# DigitalSignal.net
KiCad netlist of a schematic drawn in Altium Designer
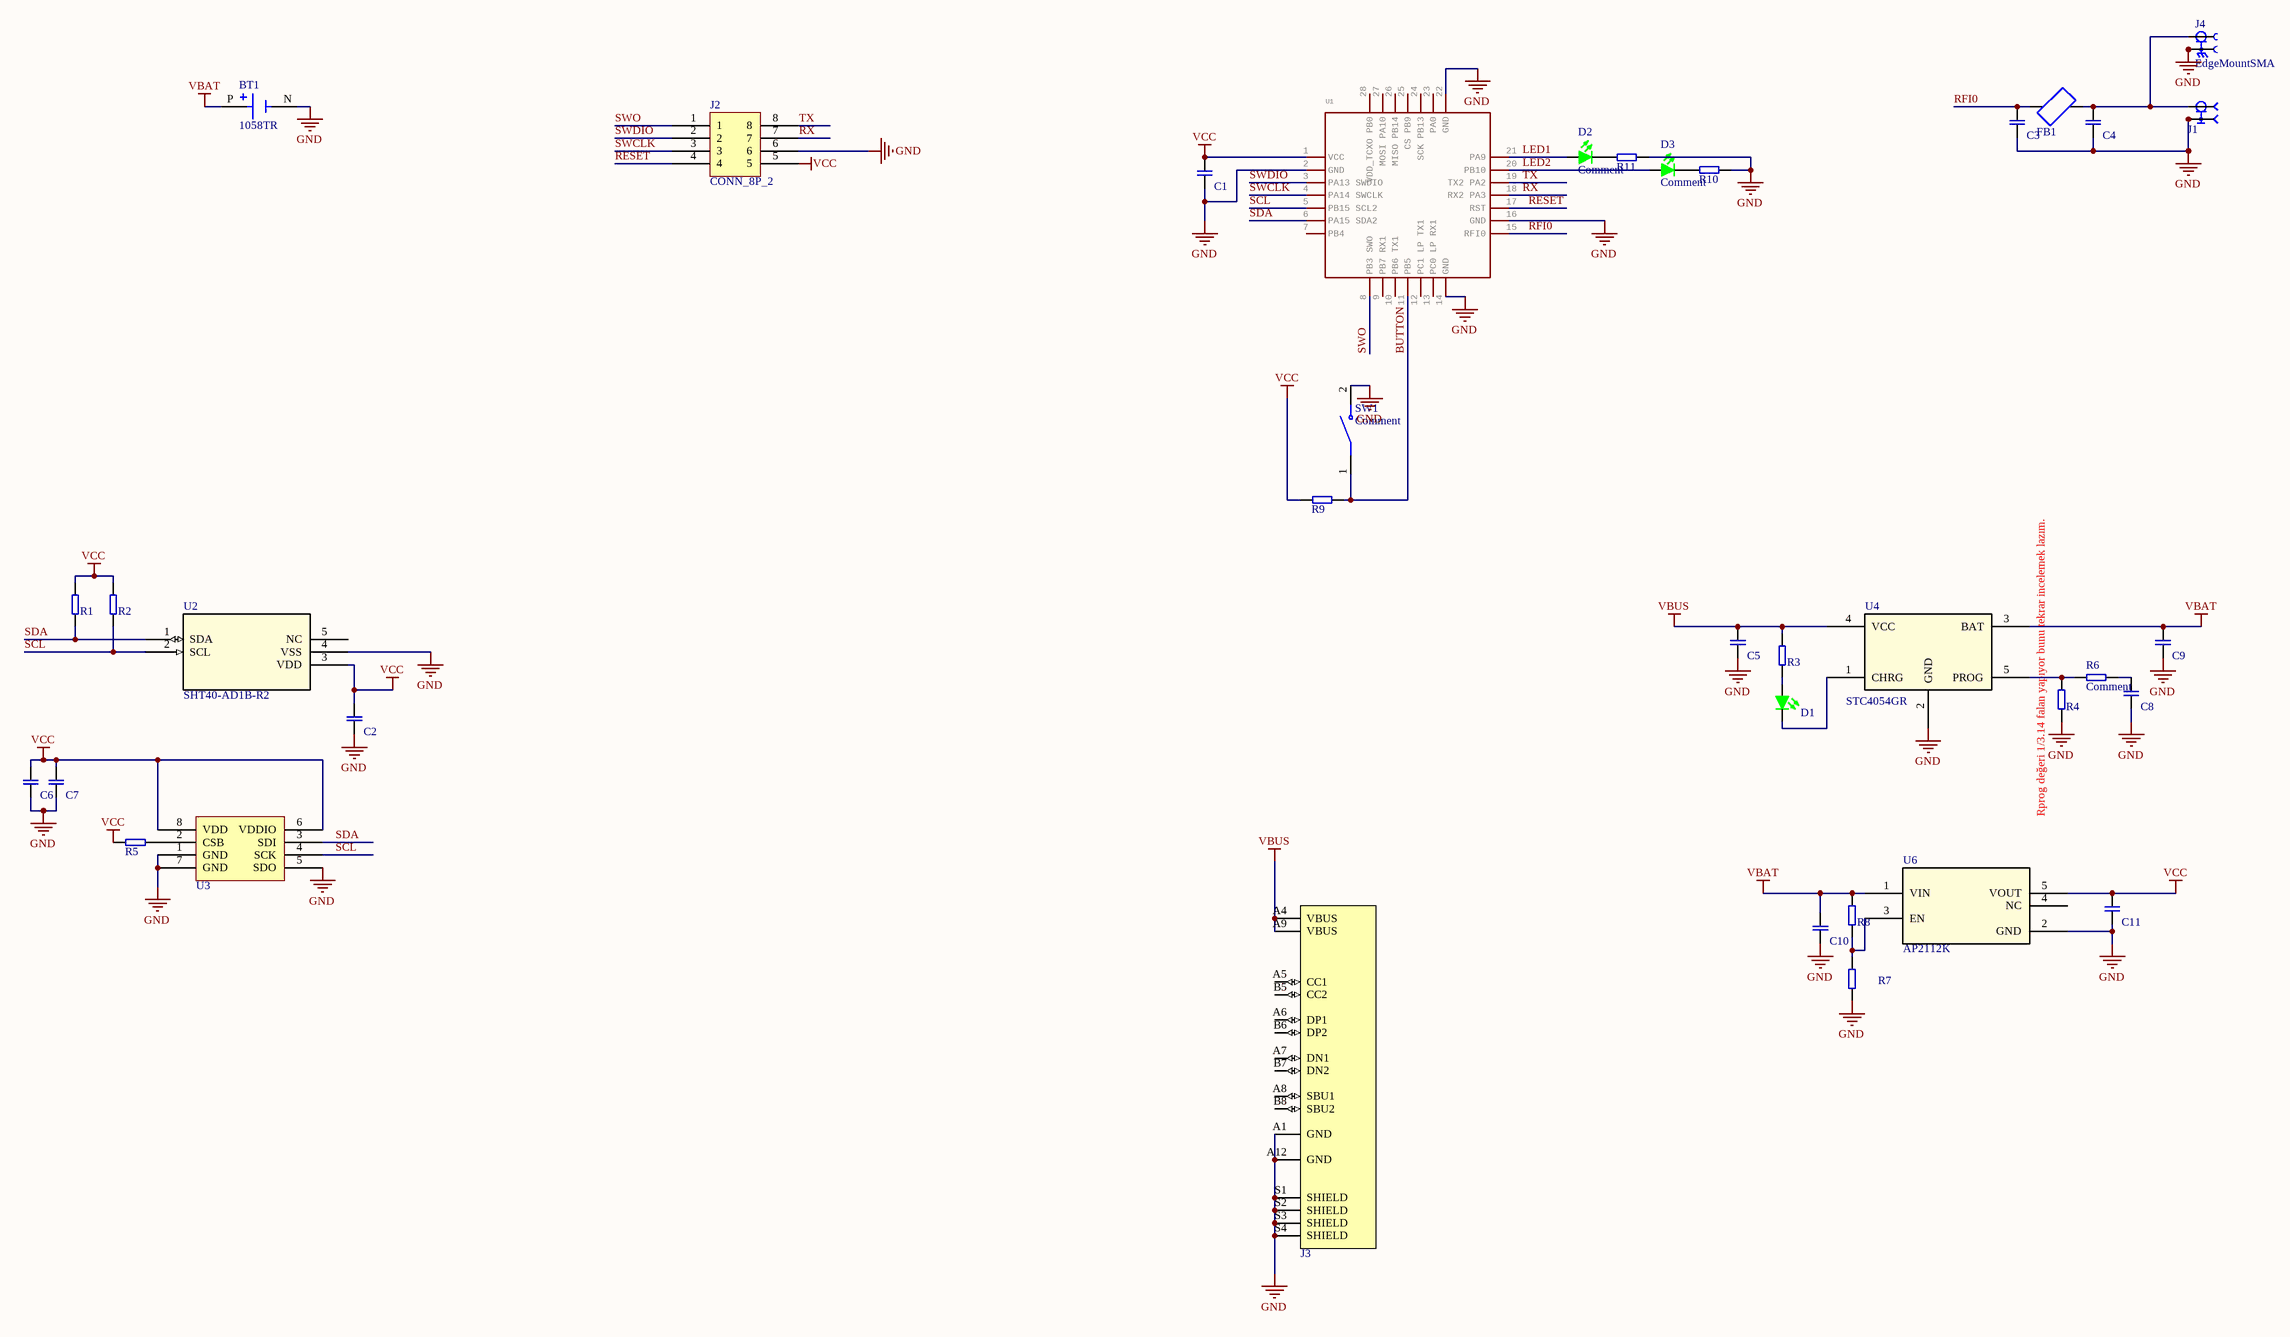
[diagram p0: DigitalSignal.SchDoc]

(export (version "E")
  (design (tool "Eeschema 10.0.6"))
  (components
    (comp (ref "BT1")
      (value "1058TR")
      (footprint "BAT_1058TR")
      (fields (field (name "PART NUMBER") "20mm_BatteryHolder"))
      (libsource (lib "anayurt") (part "1058TR"))
    )
    (comp (ref "C1")
      (value "4.7nF")
      (footprint "C0402")
      (description "CAP CER 4700PF 16V X7R 0402")
      (fields (field (name "PART NUMBER") "0402YC472KAT2A") (field (name "VOLTAGE") "16V"))
      (libsource (lib "anayurt") (part "CAP"))
    )
    (comp (ref "C2")
      (value "100nF")
      (footprint "C0402")
      (description "402")
      (fields (field (name "PART NUMBER") "CL05B104KB5NNNC"))
      (libsource (lib "anayurt") (part "CAP"))
    )
    (comp (ref "C3")
      (value "0.1uF")
      (footprint "C0402")
      (description "CAP CER 0.1UF 25V X7R 0402")
      (fields (field (name "PART NUMBER") "04023C104KAT2A") (field (name "VOLTAGE") "25V"))
      (libsource (lib "anayurt") (part "CAP"))
    )
    (comp (ref "C4")
      (value "0.1uF")
      (footprint "C0402")
      (description "CAP CER 0.1UF 25V X7R 0402")
      (fields (field (name "PART NUMBER") "04023C104KAT2A") (field (name "VOLTAGE") "25V"))
      (libsource (lib "anayurt") (part "CAP"))
    )
    (comp (ref "C5")
      (value "1uF")
      (footprint "C0603")
      (description "CAP CER 1UF 25V X7R 0603")
      (fields (field (name "PART NUMBER") "CGA3E1X7R1E105M080AC") (field (name "VOLTAGE") "25V"))
      (libsource (lib "anayurt") (part "CAP"))
    )
    (comp (ref "C6")
      (value "1uF")
      (footprint "C0402")
      (description "CAP CER 1UF 16V X5R 0402")
      (fields (field (name "PART NUMBER") "CL05A105KO5NNNC") (field (name "VOLTAGE") "16V"))
      (libsource (lib "anayurt") (part "CAP"))
    )
    (comp (ref "C7")
      (value "0.1uF")
      (footprint "C0402")
      (description "CAP CER 0.1UF 25V X7R 0402")
      (fields (field (name "PART NUMBER") "04023C104KAT2A") (field (name "VOLTAGE") "25V"))
      (libsource (lib "anayurt") (part "CAP"))
    )
    (comp (ref "C8")
      (value "100nF")
      (footprint "C0402")
      (description "402")
      (fields (field (name "PART NUMBER") "CL05B104KB5NNNC"))
      (libsource (lib "anayurt") (part "CAP"))
    )
    (comp (ref "C9")
      (value "4.7uF")
      (footprint "C0603")
      (description "CAP CER 4.7UF 25V X5R 0603")
      (fields (field (name "PART NUMBER") "C1608X5R1E475K080AC") (field (name "VOLTAGE") "25V"))
      (libsource (lib "anayurt") (part "CAP"))
    )
    (comp (ref "C10")
      (value "1uF")
      (footprint "C0402")
      (description "CAP CER 1UF 16V X5R 0402")
      (fields (field (name "PART NUMBER") "CL05A105KO5NNNC") (field (name "VOLTAGE") "16V"))
      (libsource (lib "anayurt") (part "CAP"))
    )
    (comp (ref "C11")
      (value "1uF")
      (footprint "C0402")
      (description "CAP CER 1UF 16V X5R 0402")
      (fields (field (name "PART NUMBER") "CL05A105KO5NNNC") (field (name "VOLTAGE") "16V"))
      (libsource (lib "anayurt") (part "CAP"))
    )
    (comp (ref "D1")
      (value "SML-LX0603GW-TR")
      (footprint "L0603")
      (description "LED GREEN DIFFUSED SMD")
      (fields (field (name "MANUFACTURER") "Lumex Opto/Components Inc."))
      (libsource (lib "anayurt") (part "LED_GREEN"))
    )
    (comp (ref "D2")
      (value "Comment")
      (footprint "L0805 - GREEN")
      (description "LED SMD 0805 BLUE 28-180mcd 130° WATER CLEAR")
      (fields (field (name "PART NUMBER") "LTST-S220TBKT"))
      (libsource (lib "anayurt") (part "LED_GREEN"))
    )
    (comp (ref "D3")
      (value "Comment")
      (footprint "L0805 - GREEN")
      (description "LED SMD 0805 BLUE 28-180mcd 130° WATER CLEAR")
      (fields (field (name "PART NUMBER") "LTST-S220TBKT"))
      (libsource (lib "anayurt") (part "LED_GREEN"))
    )
    (comp (ref "FB1")
      (value "30Ohm")
      (footprint "FB0603")
      (description "FERRITE BEAD 30 OHM 0603 1LN")
      (fields (field (name "PART NUMBER") "742792609") (field (name "MANUFACTURER") "Würth Elektronik"))
      (libsource (lib "anayurt") (part "FBEAD"))
    )
    (comp (ref "J1")
      (value "0734120114")
      (footprint "MOLEX_0734120114")
      (description "CONN UMC RCPT STR 50 OHM SMD")
      (fields (field (name "MANUFACTURER") "Molex"))
      (libsource (lib "anayurt") (part "SMA"))
    )
    (comp (ref "J2")
      (value "CONN_8P_2")
      (footprint "CONN_8P_1.27MM")
      (description "8P_1.27mm")
      (libsource (lib "anayurt") (part "CONN_8P_2"))
    )
    (comp (ref "J3")
      (value "TYPE-C")
      (footprint "USB4105-GF-TYPEC")
      (description "Type-C")
      (fields (field (name "MP") "USB4125-GF-A_REVA2") (field (name "PART NUMBER") "USB4105-GF-TYPEC"))
      (libsource (lib "anayurt") (part "USB4105-GF-TYPEC"))
    )
    (comp (ref "J4")
      (value "EdgeMountSMA")
      (footprint "EdgeMountSMA")
      (fields (field (name "MF") "Linx Technologies") (field (name "MP") "CONSMA020.062-G"))
      (libsource (lib "anayurt") (part "EdgeMountSMA"))
    )
    (comp (ref "R1")
      (value "1K")
      (footprint "R0402")
      (description "RES SMD 1K OHM 0.1% 1/16W 0402")
      (fields (field (name "PART NUMBER") "RT0402BRE071KL") (field (name "TOLERANCE") "0.1%"))
      (libsource (lib "anayurt") (part "RES"))
    )
    (comp (ref "R2")
      (value "1K")
      (footprint "R0402")
      (description "RES SMD 1K OHM 0.1% 1/16W 0402")
      (fields (field (name "PART NUMBER") "RT0402BRE071KL") (field (name "TOLERANCE") "0.1%"))
      (libsource (lib "anayurt") (part "RES"))
    )
    (comp (ref "R3")
      (value "1K")
      (footprint "R0402")
      (description "RES SMD 1K OHM 5% 1/16W 0402")
      (fields (field (name "PART NUMBER") "RC0402JR-071KL") (field (name "TOLERANCE") "5%"))
      (libsource (lib "anayurt") (part "RES"))
    )
    (comp (ref "R4")
      (value "330R")
      (footprint "R0603")
      (description "RES 330 OHM 1% 1/10W 0603")
      (fields (field (name "PART NUMBER") "RMCF0603FT330R") (field (name "TOLERANCE") "0.1%"))
      (libsource (lib "anayurt") (part "RES"))
    )
    (comp (ref "R5")
      (value "1K")
      (footprint "R0402")
      (description "RES SMD 1K OHM 0.1% 1/16W 0402")
      (fields (field (name "PART NUMBER") "RT0402BRE071KL") (field (name "TOLERANCE") "0.1%"))
      (libsource (lib "anayurt") (part "RES"))
    )
    (comp (ref "R6")
      (value "Comment")
      (footprint "R0402")
      (description "20K/402")
      (fields (field (name "PART NUMBER") "RC0100FR-0720KL"))
      (libsource (lib "anayurt") (part "RES"))
    )
    (comp (ref "R7")
      (value "10K")
      (footprint "R0402")
      (description "RES SMD 10K OHM 1% 1/16W 0402")
      (fields (field (name "PART NUMBER") "RC1005F103CS") (field (name "TOLERANCE") "0.1%"))
      (libsource (lib "anayurt") (part "RES"))
    )
    (comp (ref "R8")
      (value "1K")
      (footprint "R0402")
      (description "RES SMD 1K OHM 0.1% 1/16W 0402")
      (fields (field (name "PART NUMBER") "RT0402BRE071KL") (field (name "TOLERANCE") "0.1%"))
      (libsource (lib "anayurt") (part "RES"))
    )
    (comp (ref "R9")
      (value "1K")
      (footprint "R0402")
      (description "RES SMD 1K OHM 5% 1/16W 0402")
      (fields (field (name "PART NUMBER") "RC0402JR-071KL") (field (name "TOLERANCE") "5%"))
      (libsource (lib "anayurt") (part "RES"))
    )
    (comp (ref "R10")
      (value "1K")
      (footprint "R0402")
      (description "RES SMD 1K OHM 5% 1/16W 0402")
      (fields (field (name "PART NUMBER") "RC0402JR-071KL") (field (name "TOLERANCE") "5%"))
      (libsource (lib "anayurt") (part "RES"))
    )
    (comp (ref "R11")
      (value "1K")
      (footprint "R0402")
      (description "RES SMD 1K OHM 5% 1/16W 0402")
      (fields (field (name "PART NUMBER") "RC0402JR-071KL") (field (name "TOLERANCE") "5%"))
      (libsource (lib "anayurt") (part "RES"))
    )
    (comp (ref "SW1")
      (value "Comment")
      (footprint "SW_B3U-3000P-B_OMR")
      (description "SW_B3U-3000P-B_OMR")
      (fields (field (name "MANUFACTURER") "Omron") (field (name "MANUFACTURER PART NUMBER") "B3U-3000PM-B"))
      (libsource (lib "anayurt") (part "2P_Switch"))
    )
    (comp (ref "U1")
      (value "Wio-E5")
      (footprint "Wio-E5")
      (description "Seeed Lora Module")
      (fields (field (name "MANUFACTURER") "Seeed") (field (name "LIBRARYNAME") "LORA-E5_Eagle_Library"))
      (libsource (lib "anayurt") (part "Wio-E5"))
    )
    (comp (ref "U2")
      (value "SHT40-AD1B-R2")
      (footprint "SHT4x_SEN-M")
      (fields
        (field (name "PART NUMBER") "SHT40")
        (field (name "COPYRIGHT") "Copyright (C) 2023 Ultra Librarian. All rights reserved.")
      )
      (libsource (lib "anayurt") (part "SHT40-AD1B-R2"))
    )
    (comp (ref "U3")
      (value "BMP280")
      (footprint "BOSCH_BMP280")
      (description "SENSOR PRESSURE ABS")
      (fields (field (name "MANUFACTURER") "Bosch Sensortec"))
      (libsource (lib "anayurt") (part "BMP280"))
    )
    (comp (ref "U4")
      (value "STC4054GR")
      (footprint "SOP_TSOT23-5L_STM-L")
      (description "Battery Charger IC")
      (libsource (lib "anayurt") (part "STC4054GR"))
    )
    (comp (ref "U6")
      (value "AP2112K")
      (footprint "AP2112K")
      (description "LDO ADJ 3V3")
      (fields
        (field (name "MANUFACTURER") "Diodes Incorporated")
        (field (name "MANUFACTURER PART NUMBER") "AP2112K-3.3TRG1")
      )
      (libsource (lib "anayurt") (part "AP2112K"))
    )
  )
  (nets
    (net (code "1") (name "/BUTTON") (class "Default")
      (node (ref "R9") (pin "2") (pinfunction "2_2") (pintype "passive"))
      (node (ref "SW1") (pin "1") (pinfunction "1_1") (pintype "passive"))
      (node (ref "U1") (pin "11") (pinfunction "PB5_11") (pintype "bidirectional"))
    )
    (net (code "2") (name "/LED1") (class "Default")
      (node (ref "D2") (pin "A") (pinfunction "A_A") (pintype "passive"))
      (node (ref "U1") (pin "21") (pinfunction "PA9_21") (pintype "bidirectional"))
    )
    (net (code "3") (name "/LED2") (class "Default")
      (node (ref "D3") (pin "A") (pinfunction "A_A") (pintype "passive"))
      (node (ref "U1") (pin "20") (pinfunction "PB10_20") (pintype "bidirectional"))
    )
    (net (code "4") (name "/RESET") (class "Default")
      (node (ref "J2") (pin "4") (pinfunction "4_4") (pintype "passive"))
      (node (ref "U1") (pin "17") (pinfunction "RST_17") (pintype "bidirectional"))
    )
    (net (code "5") (name "/RFI0") (class "Default")
      (node (ref "C3") (pin "2") (pinfunction "2_2") (pintype "passive"))
      (node (ref "FB1") (pin "1") (pinfunction "1_1") (pintype "passive"))
      (node (ref "U1") (pin "15") (pinfunction "RFI0_15") (pintype "bidirectional"))
    )
    (net (code "6") (name "/RX") (class "Default")
      (node (ref "J2") (pin "7") (pinfunction "7_7") (pintype "passive"))
      (node (ref "U1") (pin "18") (pinfunction "RX2_PA3_18") (pintype "bidirectional"))
    )
    (net (code "7") (name "/SCL") (class "Default")
      (node (ref "R2") (pin "1") (pinfunction "1_1") (pintype "passive"))
      (node (ref "U1") (pin "5") (pinfunction "PB15_SCL2_5") (pintype "bidirectional"))
      (node (ref "U2") (pin "2") (pinfunction "SCL_2") (pintype "input"))
      (node (ref "U3") (pin "4") (pinfunction "SCK_4") (pintype "passive"))
    )
    (net (code "8") (name "/SDA") (class "Default")
      (node (ref "R1") (pin "1") (pinfunction "1_1") (pintype "passive"))
      (node (ref "U1") (pin "6") (pinfunction "PA15_SDA2_6") (pintype "bidirectional"))
      (node (ref "U2") (pin "1") (pinfunction "SDA_1") (pintype "bidirectional"))
      (node (ref "U3") (pin "3") (pinfunction "SDI_3") (pintype "passive"))
    )
    (net (code "9") (name "/SWCLK") (class "Default")
      (node (ref "J2") (pin "3") (pinfunction "3_3") (pintype "passive"))
      (node (ref "U1") (pin "4") (pinfunction "PA14_SWCLK_4") (pintype "bidirectional"))
    )
    (net (code "10") (name "/SWDIO") (class "Default")
      (node (ref "J2") (pin "2") (pinfunction "2_2") (pintype "passive"))
      (node (ref "U1") (pin "3") (pinfunction "PA13_SWDIO_3") (pintype "bidirectional"))
    )
    (net (code "11") (name "/SWO") (class "Default")
      (node (ref "J2") (pin "1") (pinfunction "1_1") (pintype "passive"))
      (node (ref "U1") (pin "8") (pinfunction "PB3_SWO_8") (pintype "bidirectional"))
    )
    (net (code "12") (name "/TX") (class "Default")
      (node (ref "J2") (pin "8") (pinfunction "8_8") (pintype "passive"))
      (node (ref "U1") (pin "19") (pinfunction "TX2_PA2_19") (pintype "bidirectional"))
    )
    (net (code "13") (name "GND") (class "Default")
      (node (ref "BT1") (pin "N") (pinfunction "NEG_N") (pintype "passive"))
      (node (ref "C1") (pin "1") (pinfunction "1_1") (pintype "passive"))
      (node (ref "C10") (pin "1") (pinfunction "1_1") (pintype "passive"))
      (node (ref "C11") (pin "1") (pinfunction "1_1") (pintype "passive"))
      (node (ref "C2") (pin "1") (pinfunction "1_1") (pintype "passive"))
      (node (ref "C3") (pin "1") (pinfunction "1_1") (pintype "passive"))
      (node (ref "C4") (pin "1") (pinfunction "1_1") (pintype "passive"))
      (node (ref "C5") (pin "1") (pinfunction "1_1") (pintype "passive"))
      (node (ref "C6") (pin "1") (pinfunction "1_1") (pintype "passive"))
      (node (ref "C7") (pin "1") (pinfunction "1_1") (pintype "passive"))
      (node (ref "C8") (pin "1") (pinfunction "1_1") (pintype "passive"))
      (node (ref "C9") (pin "1") (pinfunction "1_1") (pintype "passive"))
      (node (ref "J1") (pin "2") (pinfunction "GND_2") (pintype "power_in"))
      (node (ref "J1") (pin "3") (pinfunction "GND_3") (pintype "power_in"))
      (node (ref "J1") (pin "4") (pinfunction "GND_4") (pintype "power_in"))
      (node (ref "J2") (pin "6") (pinfunction "6_6") (pintype "passive"))
      (node (ref "J3") (pin "A1") (pinfunction "GND_A1") (pintype "power_in"))
      (node (ref "J3") (pin "A12") (pinfunction "GND_A12") (pintype "power_in"))
      (node (ref "J3") (pin "S1") (pinfunction "SHIELD_S1") (pintype "passive"))
      (node (ref "J3") (pin "S2") (pinfunction "SHIELD_S2") (pintype "passive"))
      (node (ref "J3") (pin "S3") (pinfunction "SHIELD_S3") (pintype "passive"))
      (node (ref "J3") (pin "S4") (pinfunction "SHIELD_S4") (pintype "passive"))
      (node (ref "J4") (pin "S1") (pinfunction "2_S1") (pintype "passive"))
      (node (ref "J4") (pin "S2") (pinfunction "2_S2") (pintype "passive"))
      (node (ref "J4") (pin "S3") (pinfunction "2_S3") (pintype "passive"))
      (node (ref "J4") (pin "S4") (pinfunction "2_S4") (pintype "passive"))
      (node (ref "R10") (pin "2") (pinfunction "2_2") (pintype "passive"))
      (node (ref "R11") (pin "2") (pinfunction "2_2") (pintype "passive"))
      (node (ref "R4") (pin "1") (pinfunction "1_1") (pintype "passive"))
      (node (ref "R7") (pin "1") (pinfunction "1_1") (pintype "passive"))
      (node (ref "SW1") (pin "2") (pinfunction "2_2") (pintype "passive"))
      (node (ref "U1") (pin "14") (pinfunction "GND_14") (pintype "bidirectional"))
      (node (ref "U1") (pin "16") (pinfunction "GND_16") (pintype "bidirectional"))
      (node (ref "U1") (pin "2") (pinfunction "GND_2") (pintype "bidirectional"))
      (node (ref "U1") (pin "22") (pinfunction "GND_22") (pintype "bidirectional"))
      (node (ref "U2") (pin "4") (pinfunction "VSS_4") (pintype "power_in"))
      (node (ref "U3") (pin "1") (pinfunction "GND_1") (pintype "passive"))
      (node (ref "U3") (pin "5") (pinfunction "SDO_5") (pintype "passive"))
      (node (ref "U3") (pin "7") (pinfunction "GND_7") (pintype "passive"))
      (node (ref "U4") (pin "2") (pinfunction "GND_2") (pintype "power_in"))
      (node (ref "U6") (pin "2") (pinfunction "GND_2") (pintype "passive"))
    )
    (net (code "14") (name "Net-(C8-Pad2)") (class "Default")
      (node (ref "C8") (pin "2") (pinfunction "2_2") (pintype "passive"))
      (node (ref "R6") (pin "2") (pinfunction "2_2") (pintype "passive"))
    )
    (net (code "15") (name "Net-(D1-PadA)") (class "Default")
      (node (ref "D1") (pin "A") (pinfunction "A_A") (pintype "passive"))
      (node (ref "R3") (pin "1") (pinfunction "1_1") (pintype "passive"))
    )
    (net (code "16") (name "Net-(D2-PadC)") (class "Default")
      (node (ref "D2") (pin "C") (pinfunction "C_C") (pintype "passive"))
      (node (ref "R11") (pin "1") (pinfunction "1_1") (pintype "passive"))
    )
    (net (code "17") (name "Net-(D3-PadC)") (class "Default")
      (node (ref "D3") (pin "C") (pinfunction "C_C") (pintype "passive"))
      (node (ref "R10") (pin "1") (pinfunction "1_1") (pintype "passive"))
    )
    (net (code "18") (name "Net-(J1-SIG)") (class "Default")
      (node (ref "C4") (pin "2") (pinfunction "2_2") (pintype "passive"))
      (node (ref "FB1") (pin "2") (pinfunction "2_2") (pintype "passive"))
      (node (ref "J1") (pin "1") (pinfunction "SIG_1") (pintype "passive"))
      (node (ref "J4") (pin "1") (pinfunction "1_1") (pintype "passive"))
    )
    (net (code "19") (name "Net-(U3-CSB)") (class "Default")
      (node (ref "R5") (pin "1") (pinfunction "1_1") (pintype "passive"))
      (node (ref "U3") (pin "2") (pinfunction "CSB_2") (pintype "passive"))
    )
    (net (code "20") (name "Net-(U4-CHRG)") (class "Default")
      (node (ref "D1") (pin "C") (pinfunction "C_C") (pintype "passive"))
      (node (ref "U4") (pin "1") (pinfunction "CHRG_1") (pintype "passive"))
    )
    (net (code "21") (name "Net-(U4-PROG)") (class "Default")
      (node (ref "R4") (pin "2") (pinfunction "2_2") (pintype "passive"))
      (node (ref "R6") (pin "1") (pinfunction "1_1") (pintype "passive"))
      (node (ref "U4") (pin "5") (pinfunction "PROG_5") (pintype "passive"))
    )
    (net (code "22") (name "Net-(U6-EN)") (class "Default")
      (node (ref "R7") (pin "2") (pinfunction "2_2") (pintype "passive"))
      (node (ref "R8") (pin "1") (pinfunction "1_1") (pintype "passive"))
      (node (ref "U6") (pin "3") (pinfunction "EN_3") (pintype "passive"))
    )
    (net (code "23") (name "VBAT") (class "Default")
      (node (ref "BT1") (pin "P") (pinfunction "POS_P") (pintype "passive"))
      (node (ref "C10") (pin "2") (pinfunction "2_2") (pintype "passive"))
      (node (ref "C9") (pin "2") (pinfunction "2_2") (pintype "passive"))
      (node (ref "R8") (pin "2") (pinfunction "2_2") (pintype "passive"))
      (node (ref "U4") (pin "3") (pinfunction "BAT_3") (pintype "passive"))
      (node (ref "U6") (pin "1") (pinfunction "VIN_1") (pintype "passive"))
    )
    (net (code "24") (name "VBUS") (class "Default")
      (node (ref "C5") (pin "2") (pinfunction "2_2") (pintype "passive"))
      (node (ref "J3") (pin "A4") (pinfunction "VBUS_A4") (pintype "passive"))
      (node (ref "J3") (pin "A9") (pinfunction "VBUS_A9") (pintype "power_in"))
      (node (ref "R3") (pin "2") (pinfunction "2_2") (pintype "passive"))
      (node (ref "U4") (pin "4") (pinfunction "VCC_4") (pintype "power_in"))
    )
    (net (code "25") (name "VCC") (class "Default")
      (node (ref "C1") (pin "2") (pinfunction "2_2") (pintype "passive"))
      (node (ref "C11") (pin "2") (pinfunction "2_2") (pintype "passive"))
      (node (ref "C2") (pin "2") (pinfunction "2_2") (pintype "passive"))
      (node (ref "C6") (pin "2") (pinfunction "2_2") (pintype "passive"))
      (node (ref "C7") (pin "2") (pinfunction "2_2") (pintype "passive"))
      (node (ref "J2") (pin "5") (pinfunction "5_5") (pintype "passive"))
      (node (ref "R1") (pin "2") (pinfunction "2_2") (pintype "passive"))
      (node (ref "R2") (pin "2") (pinfunction "2_2") (pintype "passive"))
      (node (ref "R5") (pin "2") (pinfunction "2_2") (pintype "passive"))
      (node (ref "R9") (pin "1") (pinfunction "1_1") (pintype "passive"))
      (node (ref "U1") (pin "1") (pinfunction "VCC_1") (pintype "bidirectional"))
      (node (ref "U2") (pin "3") (pinfunction "VDD_3") (pintype "power_in"))
      (node (ref "U3") (pin "6") (pinfunction "VDDIO_6") (pintype "passive"))
      (node (ref "U3") (pin "8") (pinfunction "VDD_8") (pintype "passive"))
      (node (ref "U6") (pin "5") (pinfunction "VOUT_5") (pintype "passive"))
    )
    (net (code "26") (name "unconnected-(J3-CC1-PadA5)") (class "Default")
      (node (ref "J3") (pin "A5") (pinfunction "CC1_A5") (pintype "bidirectional"))
    )
    (net (code "27") (name "unconnected-(J3-CC2-PadB5)") (class "Default")
      (node (ref "J3") (pin "B5") (pinfunction "CC2_B5") (pintype "bidirectional"))
    )
    (net (code "28") (name "unconnected-(J3-DN1-PadA7)") (class "Default")
      (node (ref "J3") (pin "A7") (pinfunction "DN1_A7") (pintype "bidirectional"))
    )
    (net (code "29") (name "unconnected-(J3-DN2-PadB7)") (class "Default")
      (node (ref "J3") (pin "B7") (pinfunction "DN2_B7") (pintype "bidirectional"))
    )
    (net (code "30") (name "unconnected-(J3-DP1-PadA6)") (class "Default")
      (node (ref "J3") (pin "A6") (pinfunction "DP1_A6") (pintype "bidirectional"))
    )
    (net (code "31") (name "unconnected-(J3-DP2-PadB6)") (class "Default")
      (node (ref "J3") (pin "B6") (pinfunction "DP2_B6") (pintype "bidirectional"))
    )
    (net (code "32") (name "unconnected-(J3-SBU1-PadA8)") (class "Default")
      (node (ref "J3") (pin "A8") (pinfunction "SBU1_A8") (pintype "bidirectional"))
    )
    (net (code "33") (name "unconnected-(J3-SBU2-PadB8)") (class "Default")
      (node (ref "J3") (pin "B8") (pinfunction "SBU2_B8") (pintype "bidirectional"))
    )
    (net (code "34") (name "unconnected-(U1-CS_PB9-Pad25)") (class "Default")
      (node (ref "U1") (pin "25") (pinfunction "CS_PB9_25") (pintype "bidirectional"))
    )
    (net (code "35") (name "unconnected-(U1-MISO_PB14-Pad26)") (class "Default")
      (node (ref "U1") (pin "26") (pinfunction "MISO_PB14_26") (pintype "bidirectional"))
    )
    (net (code "36") (name "unconnected-(U1-MOSI_PA10-Pad27)") (class "Default")
      (node (ref "U1") (pin "27") (pinfunction "MOSI_PA10_27") (pintype "bidirectional"))
    )
    (net (code "37") (name "unconnected-(U1-PA0-Pad23)") (class "Default")
      (node (ref "U1") (pin "23") (pinfunction "PA0_23") (pintype "bidirectional"))
    )
    (net (code "38") (name "unconnected-(U1-PB4-Pad7)") (class "Default")
      (node (ref "U1") (pin "7") (pinfunction "PB4_7") (pintype "bidirectional"))
    )
    (net (code "39") (name "unconnected-(U1-PB6_TX1-Pad10)") (class "Default")
      (node (ref "U1") (pin "10") (pinfunction "PB6_TX1_10") (pintype "bidirectional"))
    )
    (net (code "40") (name "unconnected-(U1-PB7_RX1-Pad9)") (class "Default")
      (node (ref "U1") (pin "9") (pinfunction "PB7_RX1_9") (pintype "bidirectional"))
    )
    (net (code "41") (name "unconnected-(U1-PC0_LP_RX1-Pad13)") (class "Default")
      (node (ref "U1") (pin "13") (pinfunction "PC0_LP_RX1_13") (pintype "bidirectional"))
    )
    (net (code "42") (name "unconnected-(U1-PC1_LP_TX1-Pad12)") (class "Default")
      (node (ref "U1") (pin "12") (pinfunction "PC1_LP_TX1_12") (pintype "bidirectional"))
    )
    (net (code "43") (name "unconnected-(U1-SCK_PB13-Pad24)") (class "Default")
      (node (ref "U1") (pin "24") (pinfunction "SCK_PB13_24") (pintype "bidirectional"))
    )
    (net (code "44") (name "unconnected-(U1-VDD_TCXO_PB0-Pad28)") (class "Default")
      (node (ref "U1") (pin "28") (pinfunction "VDD_TCXO_PB0_28") (pintype "bidirectional"))
    )
    (net (code "45") (name "unconnected-(U2-NC-Pad5)") (class "Default")
      (node (ref "U2") (pin "5") (pinfunction "NC_5") (pintype "passive"))
    )
    (net (code "46") (name "unconnected-(U6-NC-Pad4)") (class "Default")
      (node (ref "U6") (pin "4") (pinfunction "NC_4") (pintype "passive"))
    )
  )
)
